# POWER.net
KiCad netlist of a schematic drawn in Altium Designer
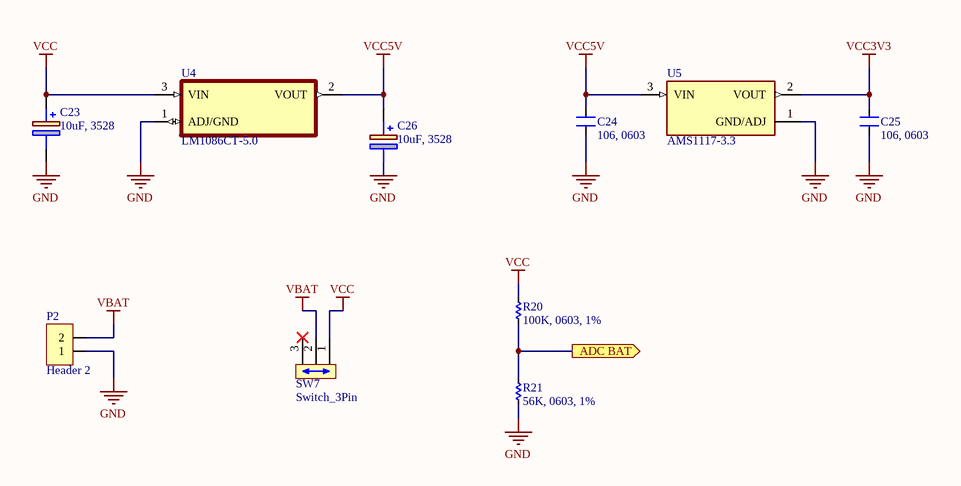
[diagram p0: POWER.SchDoc]

(export (version "E")
  (design (tool "Eeschema 10.0.6"))
  (components
    (comp (ref "C23")
      (value "10uF, 3528")
      (footprint "CAP-TANTAL-3528")
      (description "Tantalum Capacitor")
      (libsource (lib "LIB_Project2") (part "CAP Tantalum"))
    )
    (comp (ref "C24")
      (value "106, 0603")
      (footprint "SM-0603")
      (description "Cap SMD")
      (libsource (lib "KhanhBK_Library_4") (part "CM"))
    )
    (comp (ref "C25")
      (value "106, 0603")
      (footprint "SM-0603")
      (description "Cap SMD")
      (libsource (lib "KhanhBK_Library_4") (part "CM"))
    )
    (comp (ref "C26")
      (value "10uF, 3528")
      (footprint "CAP-TANTAL-3528")
      (description "Tantalum Capacitor")
      (libsource (lib "LIB_Project2") (part "CAP Tantalum"))
    )
    (comp (ref "P2")
      (value "Header 2")
      (footprint "HDR/Header/2")
      (description "Header, 2-Pin")
      (libsource (lib "connectors") (part "Header 2"))
    )
    (comp (ref "R20")
      (value "100K, 0603, 1%")
      (footprint "RES-SMD-0603")
      (description "Resistor")
      (fields
        (field (name "MANUFACTURER") "Generic Components")
        (field (name "PUBLISHER") "Altium Hobart Technology Centre")
      )
      (libsource (lib "KhanhBK_SCH_Library_1") (part "Res-SMD"))
    )
    (comp (ref "R21")
      (value "56K, 0603, 1%")
      (footprint "RES-SMD-0603")
      (description "Resistor")
      (fields
        (field (name "MANUFACTURER") "Generic Components")
        (field (name "PUBLISHER") "Altium Hobart Technology Centre")
      )
      (libsource (lib "KhanhBK_SCH_Library_1") (part "Res-SMD"))
    )
    (comp (ref "SW7")
      (value "Switch_3Pin")
      (footprint "SW-12F23")
      (description "Switch")
      (fields (field (name "PUBLISHER") "Altium Limited"))
      (libsource (lib "KhanhBK_SCH_Lib_5") (part "Switch_3Pin"))
    )
    (comp (ref "U4")
      (value "LM1086CT-5.0")
      (footprint "TO254P1054X470X1955-3")
      (fields
        (field (name "MF") "{'manufacturer': u'Texas Instruments'}")
        (field (name "MP") "LM1086CT-5.0/NOPB")
      )
      (libsource (lib "SnapEDA_Library") (part "LM1086CT-5.0"))
    )
    (comp (ref "U5")
      (value "AMS1117-3.3")
      (footprint "SOT229P700X180-4N")
      (fields (field (name "MF") "{'manufacturer': u'Advanced Monolithic Systems'}"))
      (libsource (lib "SnapEDA_Library") (part "AMS1117-3.3"))
    )
  )
  (nets
    (net (code "1") (name "/ADC BAT") (class "Default")
      (node (ref "R20") (pin "2") (pinfunction "2_2") (pintype "passive"))
      (node (ref "R21") (pin "1") (pinfunction "1_1") (pintype "passive"))
    )
    (net (code "2") (name "GND") (class "Default")
      (node (ref "C23") (pin "2") (pinfunction "2_2") (pintype "passive"))
      (node (ref "C24") (pin "1") (pinfunction "1_1") (pintype "passive"))
      (node (ref "C25") (pin "1") (pinfunction "1_1") (pintype "passive"))
      (node (ref "C26") (pin "2") (pinfunction "2_2") (pintype "passive"))
      (node (ref "P2") (pin "1") (pinfunction "1_1") (pintype "passive"))
      (node (ref "R21") (pin "2") (pinfunction "2_2") (pintype "passive"))
      (node (ref "U4") (pin "1") (pinfunction "ADJ/GND_1") (pintype "bidirectional"))
      (node (ref "U5") (pin "1") (pinfunction "GND/ADJ_1") (pintype "power_in"))
    )
    (net (code "3") (name "VBAT") (class "Default")
      (node (ref "P2") (pin "2") (pinfunction "2_2") (pintype "passive"))
      (node (ref "SW7") (pin "2") (pinfunction "COMMON_2") (pintype "passive"))
    )
    (net (code "4") (name "VCC") (class "Default")
      (node (ref "C23") (pin "1") (pinfunction "1_1") (pintype "passive"))
      (node (ref "R20") (pin "1") (pinfunction "1_1") (pintype "passive"))
      (node (ref "SW7") (pin "1") (pinfunction "1_1") (pintype "passive"))
      (node (ref "U4") (pin "3") (pinfunction "VIN_3") (pintype "input"))
    )
    (net (code "5") (name "VCC3V3") (class "Default")
      (node (ref "C25") (pin "2") (pinfunction "2_2") (pintype "passive"))
      (node (ref "U5") (pin "2") (pinfunction "VOUT_2") (pintype "output"))
    )
    (net (code "6") (name "VCC5V") (class "Default")
      (node (ref "C24") (pin "2") (pinfunction "2_2") (pintype "passive"))
      (node (ref "C26") (pin "1") (pinfunction "1_1") (pintype "passive"))
      (node (ref "U4") (pin "2") (pinfunction "VOUT_2") (pintype "output"))
      (node (ref "U5") (pin "3") (pinfunction "VIN_3") (pintype "input"))
    )
    (net (code "7") (name "unconnected-(SW7-Pad3)") (class "Default")
      (node (ref "SW7") (pin "3") (pinfunction "3_3") (pintype "passive+no_connect"))
    )
  )
)
